# SCH_Gps_sim_locator_2022-06-02.net
KiCad netlist of a schematic drawn in EasyEDA
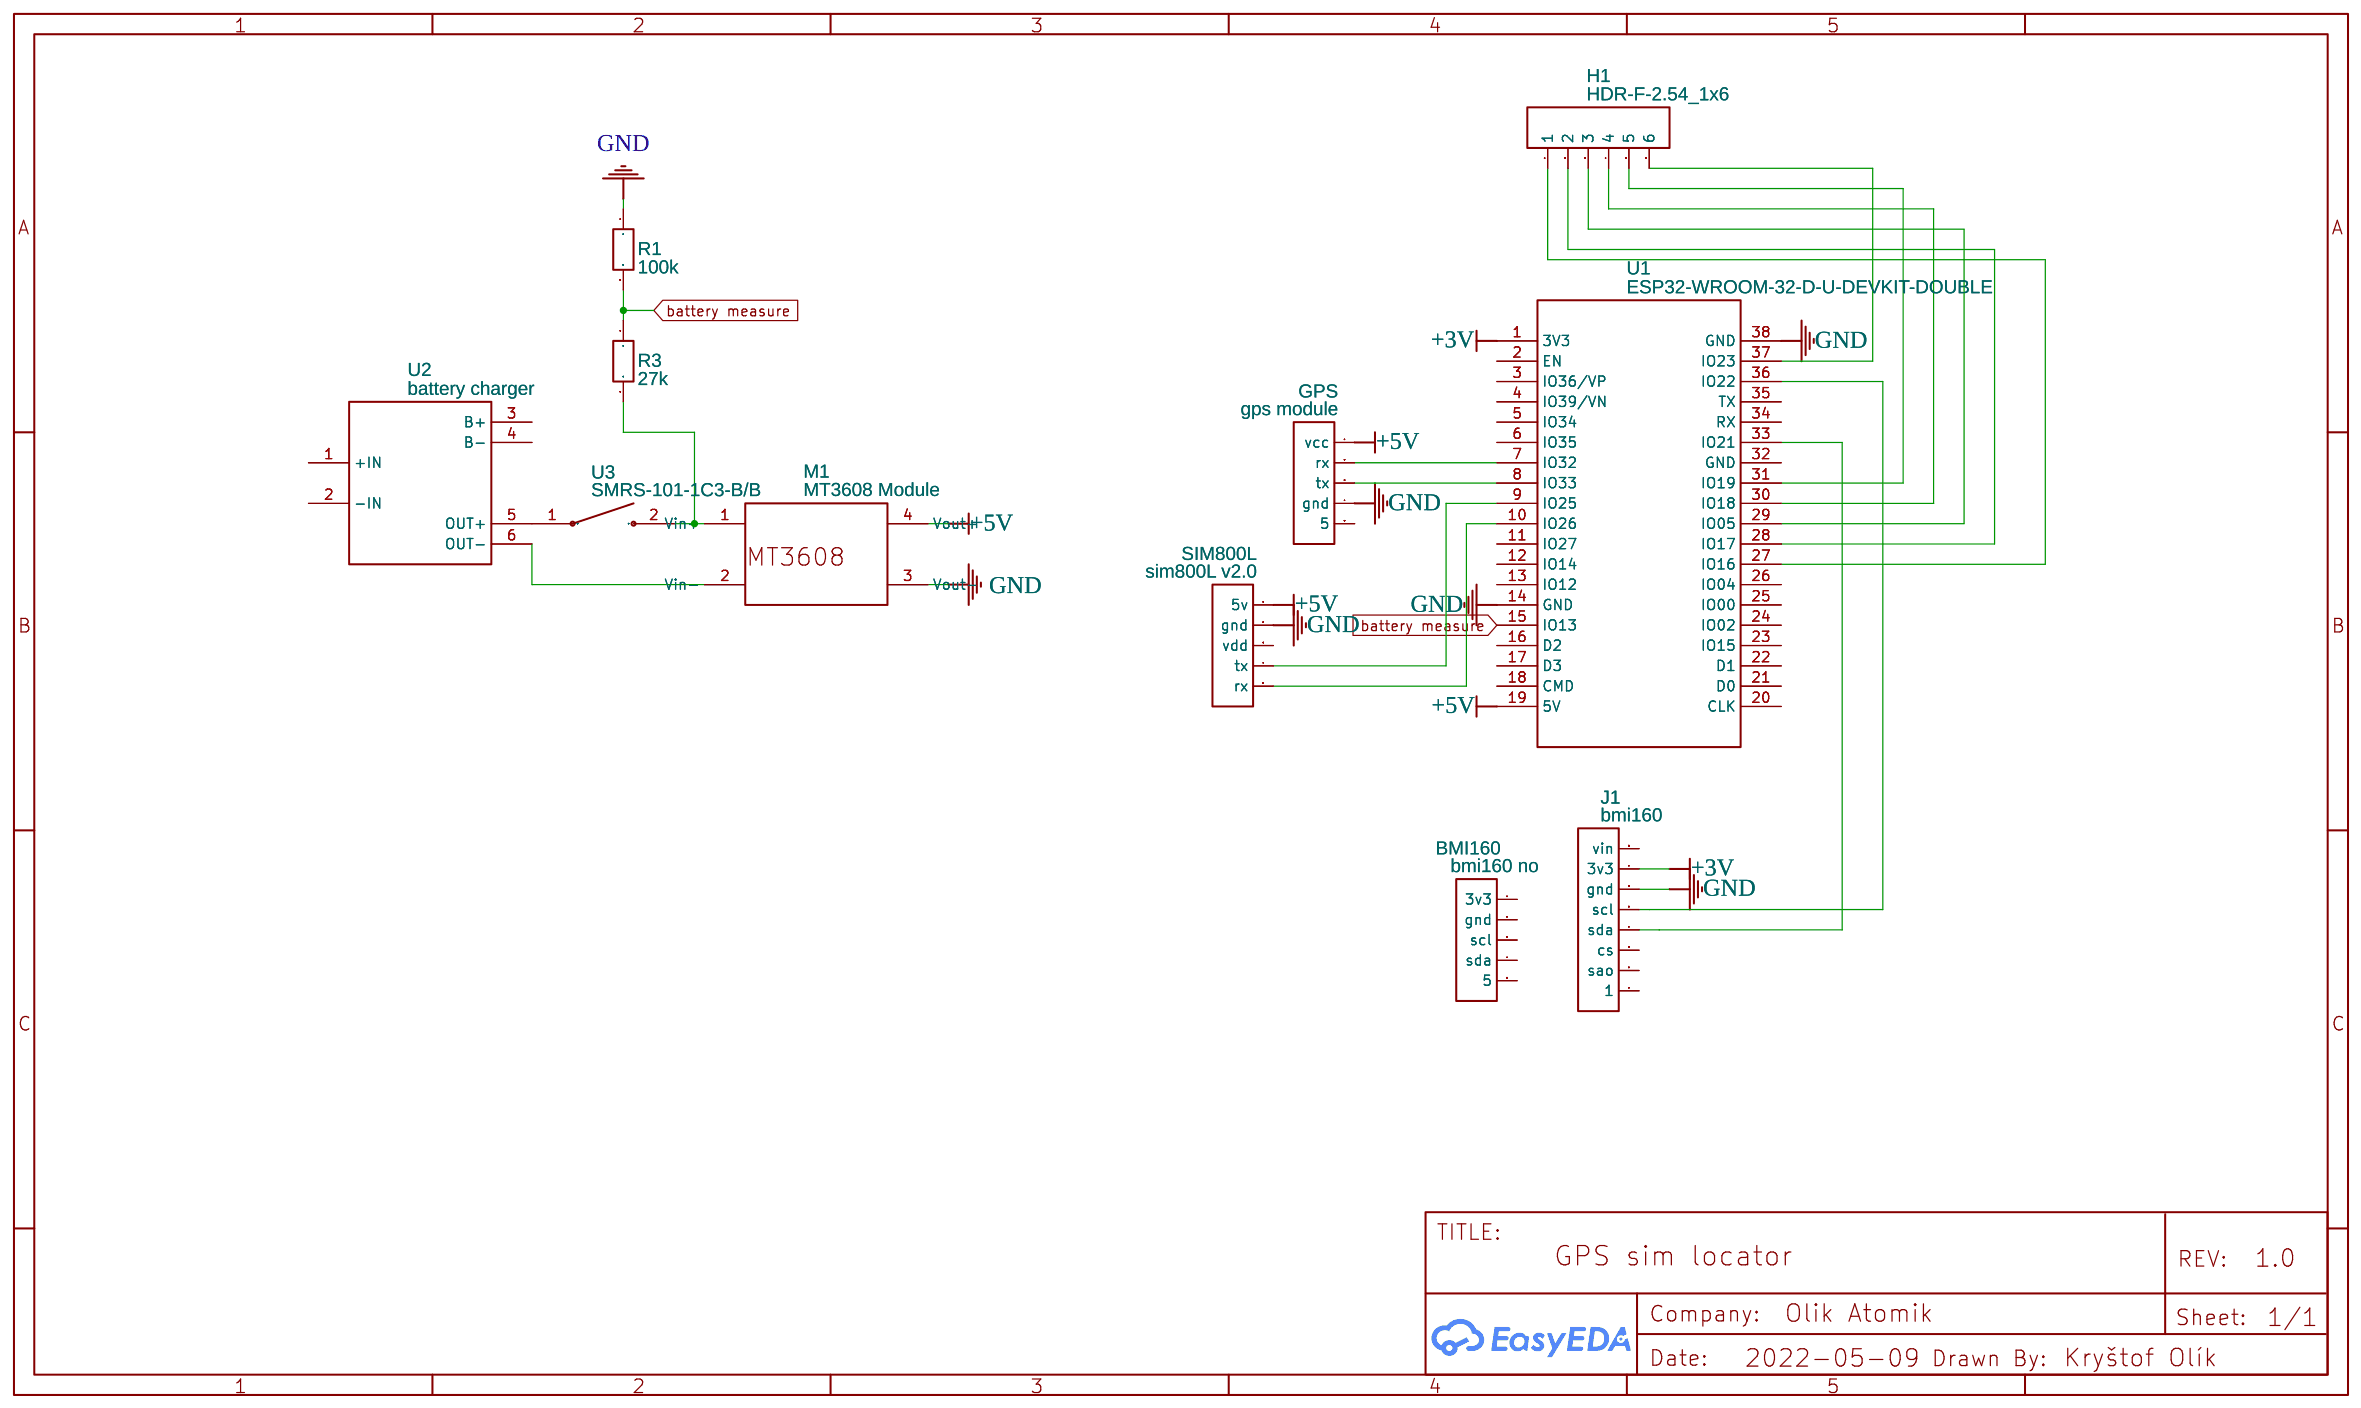
[diagram p0: schematic sheet]

(export (version "E")
  (design (tool "Eeschema 10.0.6"))
  (components
    (comp (ref "BMI160")
      (value "bmi160 no")
      (fields (field (name "BOM_Supplier Part") "C50950"))
      (libsource (lib "") (part "HDR-F-2.54_1x5_1"))
    )
    (comp (ref "GPS")
      (value "gps module")
      (fields (field (name "BOM_Supplier Part") "C50950"))
      (libsource (lib "") (part "HDR-F-2.54_1x5_2"))
    )
    (comp (ref "H1")
      (value "HDR-F-2.54_1x6")
      (fields (field (name "BOM_Supplier Part") "C40877"))
      (libsource (lib "") (part "HDR-F-2.54_1x6"))
    )
    (comp (ref "J1")
      (value "bmi160")
      (fields (field (name "BOM_Supplier Part") "C190820"))
      (libsource (lib "") (part "HDR-M-2.54_1x8"))
    )
    (comp (ref "M1") (value "MT3608 Module") (libsource (lib "") (part "MT3608 Module")))
    (comp (ref "R1") (value "100k") (libsource (lib "") (part "R_AXIAL-0.3_EU")))
    (comp (ref "R3") (value "27k") (libsource (lib "") (part "R_AXIAL-0.3_EU")))
    (comp (ref "SIM800L")
      (value "sim800L v2.0")
      (fields (field (name "BOM_Supplier Part") "C50950"))
      (libsource (lib "") (part "HDR-F-2.54_1x5"))
    )
    (comp (ref "U1")
      (value "ESP32-WROOM-32-D-U-DEVKIT-DOUBLE")
      (libsource (lib "") (part "ESP32-WROOM-32-D-U-DEVKIT-DOUBLE"))
    )
    (comp (ref "U2") (value "battery charger") (libsource (lib "") (part "TP4056 COPY")))
    (comp (ref "U3") (value "SMRS-101-1C3-B/B") (libsource (lib "") (part "SMRS-101-1C3-B/B")))
  )
  (nets
    (net (code "1") (name "+3V") (class "Default")
      (node (ref "J1") (pin "7") (pinfunction "3v3_7") (pintype "unspecified"))
      (node (ref "U1") (pin "1") (pinfunction "3V3_1") (pintype "unspecified"))
    )
    (net (code "2") (name "+5V") (class "Default")
      (node (ref "GPS") (pin "1") (pinfunction "vcc_1") (pintype "unspecified"))
      (node (ref "M1") (pin "4") (pinfunction "Vout+_4") (pintype "unspecified"))
      (node (ref "SIM800L") (pin "1") (pinfunction "5v_1") (pintype "unspecified"))
      (node (ref "U1") (pin "19") (pinfunction "5V_19") (pintype "unspecified"))
    )
    (net (code "3") (name "GND") (class "Default")
      (node (ref "GPS") (pin "4") (pinfunction "gnd_4") (pintype "unspecified"))
      (node (ref "J1") (pin "6") (pinfunction "gnd_6") (pintype "unspecified"))
      (node (ref "M1") (pin "3") (pinfunction "Vout-_3") (pintype "unspecified"))
      (node (ref "R1") (pin "1") (pinfunction "1_1") (pintype "unspecified"))
      (node (ref "SIM800L") (pin "2") (pinfunction "gnd_2") (pintype "unspecified"))
      (node (ref "U1") (pin "14") (pinfunction "GND_14") (pintype "unspecified"))
      (node (ref "U1") (pin "38") (pinfunction "GND_38") (pintype "unspecified"))
    )
    (net (code "4") (name "Net-(GPS-rx)") (class "Default")
      (node (ref "GPS") (pin "2") (pinfunction "rx_2") (pintype "unspecified"))
      (node (ref "U1") (pin "7") (pinfunction "IO32_7") (pintype "unspecified"))
    )
    (net (code "5") (name "Net-(GPS-tx)") (class "Default")
      (node (ref "GPS") (pin "3") (pinfunction "tx_3") (pintype "unspecified"))
      (node (ref "U1") (pin "8") (pinfunction "IO33_8") (pintype "unspecified"))
    )
    (net (code "6") (name "Net-(J1-scl)") (class "Default")
      (node (ref "J1") (pin "5") (pinfunction "scl_5") (pintype "unspecified"))
      (node (ref "U1") (pin "36") (pinfunction "IO22_36") (pintype "unspecified"))
    )
    (net (code "7") (name "Net-(J1-sda)") (class "Default")
      (node (ref "J1") (pin "4") (pinfunction "sda_4") (pintype "unspecified"))
      (node (ref "U1") (pin "33") (pinfunction "IO21_33") (pintype "unspecified"))
    )
    (net (code "8") (name "Net-(M1-Vin-)") (class "Default")
      (node (ref "M1") (pin "2") (pinfunction "Vin-_2") (pintype "unspecified"))
      (node (ref "U2") (pin "6") (pinfunction "OUT-_6") (pintype "unspecified"))
    )
    (net (code "9") (name "Net-(R3-Pad2)") (class "Default")
      (node (ref "R3") (pin "2") (pinfunction "2_2") (pintype "unspecified"))
      (node (ref "U3") (pin "2") (pinfunction "2_2") (pintype "unspecified"))
    )
    (net (code "10") (name "Net-(SIM800L-rx)") (class "Default")
      (node (ref "SIM800L") (pin "5") (pinfunction "rx_5") (pintype "unspecified"))
      (node (ref "U1") (pin "10") (pinfunction "IO26_10") (pintype "unspecified"))
    )
    (net (code "11") (name "Net-(SIM800L-tx)") (class "Default")
      (node (ref "SIM800L") (pin "4") (pinfunction "tx_4") (pintype "unspecified"))
      (node (ref "U1") (pin "9") (pinfunction "IO25_9") (pintype "unspecified"))
    )
    (net (code "12") (name "Net-(U1-IO05)") (class "Default")
      (node (ref "H1") (pin "3") (pinfunction "3_3") (pintype "input"))
      (node (ref "U1") (pin "29") (pinfunction "IO05_29") (pintype "unspecified"))
    )
    (net (code "13") (name "Net-(U1-IO16)") (class "Default")
      (node (ref "H1") (pin "1") (pinfunction "1_1") (pintype "input"))
      (node (ref "U1") (pin "27") (pinfunction "IO16_27") (pintype "unspecified"))
    )
    (net (code "14") (name "Net-(U1-IO17)") (class "Default")
      (node (ref "H1") (pin "2") (pinfunction "2_2") (pintype "input"))
      (node (ref "U1") (pin "28") (pinfunction "IO17_28") (pintype "unspecified"))
    )
    (net (code "15") (name "Net-(U1-IO18)") (class "Default")
      (node (ref "H1") (pin "4") (pinfunction "4_4") (pintype "input"))
      (node (ref "U1") (pin "30") (pinfunction "IO18_30") (pintype "unspecified"))
    )
    (net (code "16") (name "Net-(U1-IO19)") (class "Default")
      (node (ref "H1") (pin "5") (pinfunction "5_5") (pintype "input"))
      (node (ref "U1") (pin "31") (pinfunction "IO19_31") (pintype "unspecified"))
    )
    (net (code "17") (name "Net-(U1-IO23)") (class "Default")
      (node (ref "H1") (pin "6") (pinfunction "6_6") (pintype "input"))
      (node (ref "U1") (pin "37") (pinfunction "IO23_37") (pintype "unspecified"))
    )
    (net (code "18") (name "Net-(U2-OUT+)") (class "Default")
      (node (ref "U2") (pin "5") (pinfunction "OUT+_5") (pintype "unspecified"))
      (node (ref "U3") (pin "1") (pinfunction "in_1") (pintype "unspecified"))
    )
    (net (code "19") (name "battery measure") (class "Default")
      (node (ref "R1") (pin "2") (pinfunction "2_2") (pintype "unspecified"))
      (node (ref "R3") (pin "1") (pinfunction "1_1") (pintype "unspecified"))
      (node (ref "U1") (pin "15") (pinfunction "IO13_15") (pintype "unspecified"))
    )
    (net (code "20") (name "unconnected-(BMI160-3v3-Pad1)") (class "Default")
      (node (ref "BMI160") (pin "1") (pinfunction "3v3_1") (pintype "unspecified"))
    )
    (net (code "21") (name "unconnected-(BMI160-Pad5)") (class "Default")
      (node (ref "BMI160") (pin "5") (pinfunction "5_5") (pintype "unspecified"))
    )
    (net (code "22") (name "unconnected-(BMI160-gnd-Pad2)") (class "Default")
      (node (ref "BMI160") (pin "2") (pinfunction "gnd_2") (pintype "unspecified"))
    )
    (net (code "23") (name "unconnected-(BMI160-scl-Pad3)") (class "Default")
      (node (ref "BMI160") (pin "3") (pinfunction "scl_3") (pintype "unspecified"))
    )
    (net (code "24") (name "unconnected-(BMI160-sda-Pad4)") (class "Default")
      (node (ref "BMI160") (pin "4") (pinfunction "sda_4") (pintype "unspecified"))
    )
    (net (code "25") (name "unconnected-(GPS-Pad5)") (class "Default")
      (node (ref "GPS") (pin "5") (pinfunction "5_5") (pintype "unspecified"))
    )
    (net (code "26") (name "unconnected-(J1-Pad1)") (class "Default")
      (node (ref "J1") (pin "1") (pinfunction "1_1") (pintype "unspecified"))
    )
    (net (code "27") (name "unconnected-(J1-cs-Pad3)") (class "Default")
      (node (ref "J1") (pin "3") (pinfunction "cs_3") (pintype "unspecified"))
    )
    (net (code "28") (name "unconnected-(J1-sao-Pad2)") (class "Default")
      (node (ref "J1") (pin "2") (pinfunction "sao_2") (pintype "unspecified"))
    )
    (net (code "29") (name "unconnected-(J1-vin-Pad8)") (class "Default")
      (node (ref "J1") (pin "8") (pinfunction "vin_8") (pintype "unspecified"))
    )
    (net (code "30") (name "unconnected-(M1-Vin+-Pad1)") (class "Default")
      (node (ref "M1") (pin "1") (pinfunction "Vin+_1") (pintype "unspecified"))
    )
    (net (code "31") (name "unconnected-(SIM800L-vdd-Pad3)") (class "Default")
      (node (ref "SIM800L") (pin "3") (pinfunction "vdd_3") (pintype "unspecified"))
    )
    (net (code "32") (name "unconnected-(U1-CLK-Pad20)") (class "Default")
      (node (ref "U1") (pin "20") (pinfunction "CLK_20") (pintype "unspecified"))
    )
    (net (code "33") (name "unconnected-(U1-CMD-Pad18)") (class "Default")
      (node (ref "U1") (pin "18") (pinfunction "CMD_18") (pintype "unspecified"))
    )
    (net (code "34") (name "unconnected-(U1-D0-Pad21)") (class "Default")
      (node (ref "U1") (pin "21") (pinfunction "D0_21") (pintype "unspecified"))
    )
    (net (code "35") (name "unconnected-(U1-D1-Pad22)") (class "Default")
      (node (ref "U1") (pin "22") (pinfunction "D1_22") (pintype "unspecified"))
    )
    (net (code "36") (name "unconnected-(U1-D2-Pad16)") (class "Default")
      (node (ref "U1") (pin "16") (pinfunction "D2_16") (pintype "unspecified"))
    )
    (net (code "37") (name "unconnected-(U1-D3-Pad17)") (class "Default")
      (node (ref "U1") (pin "17") (pinfunction "D3_17") (pintype "unspecified"))
    )
    (net (code "38") (name "unconnected-(U1-EN-Pad2)") (class "Default")
      (node (ref "U1") (pin "2") (pinfunction "EN_2") (pintype "unspecified"))
    )
    (net (code "39") (name "unconnected-(U1-GND-Pad32)") (class "Default")
      (node (ref "U1") (pin "32") (pinfunction "GND_32") (pintype "unspecified"))
    )
    (net (code "40") (name "unconnected-(U1-IO00-Pad25)") (class "Default")
      (node (ref "U1") (pin "25") (pinfunction "IO00_25") (pintype "unspecified"))
    )
    (net (code "41") (name "unconnected-(U1-IO02-Pad24)") (class "Default")
      (node (ref "U1") (pin "24") (pinfunction "IO02_24") (pintype "unspecified"))
    )
    (net (code "42") (name "unconnected-(U1-IO04-Pad26)") (class "Default")
      (node (ref "U1") (pin "26") (pinfunction "IO04_26") (pintype "unspecified"))
    )
    (net (code "43") (name "unconnected-(U1-IO12-Pad13)") (class "Default")
      (node (ref "U1") (pin "13") (pinfunction "IO12_13") (pintype "unspecified"))
    )
    (net (code "44") (name "unconnected-(U1-IO14-Pad12)") (class "Default")
      (node (ref "U1") (pin "12") (pinfunction "IO14_12") (pintype "unspecified"))
    )
    (net (code "45") (name "unconnected-(U1-IO15-Pad23)") (class "Default")
      (node (ref "U1") (pin "23") (pinfunction "IO15_23") (pintype "unspecified"))
    )
    (net (code "46") (name "unconnected-(U1-IO27-Pad11)") (class "Default")
      (node (ref "U1") (pin "11") (pinfunction "IO27_11") (pintype "unspecified"))
    )
    (net (code "47") (name "unconnected-(U1-IO34-Pad5)") (class "Default")
      (node (ref "U1") (pin "5") (pinfunction "IO34_5") (pintype "unspecified"))
    )
    (net (code "48") (name "unconnected-(U1-IO35-Pad6)") (class "Default")
      (node (ref "U1") (pin "6") (pinfunction "IO35_6") (pintype "unspecified"))
    )
    (net (code "49") (name "unconnected-(U1-IO36{slash}VP-Pad3)") (class "Default")
      (node (ref "U1") (pin "3") (pinfunction "IO36/VP_3") (pintype "unspecified"))
    )
    (net (code "50") (name "unconnected-(U1-IO39{slash}VN-Pad4)") (class "Default")
      (node (ref "U1") (pin "4") (pinfunction "IO39/VN_4") (pintype "unspecified"))
    )
    (net (code "51") (name "unconnected-(U1-RX-Pad34)") (class "Default")
      (node (ref "U1") (pin "34") (pinfunction "RX_34") (pintype "unspecified"))
    )
    (net (code "52") (name "unconnected-(U1-TX-Pad35)") (class "Default")
      (node (ref "U1") (pin "35") (pinfunction "TX_35") (pintype "unspecified"))
    )
    (net (code "53") (name "unconnected-(U2-+IN-Pad1)") (class "Default")
      (node (ref "U2") (pin "1") (pinfunction "+IN_1") (pintype "unspecified"))
    )
    (net (code "54") (name "unconnected-(U2--IN-Pad2)") (class "Default")
      (node (ref "U2") (pin "2") (pinfunction "-IN_2") (pintype "unspecified"))
    )
    (net (code "55") (name "unconnected-(U2-B+-Pad3)") (class "Default")
      (node (ref "U2") (pin "3") (pinfunction "B+_3") (pintype "unspecified"))
    )
    (net (code "56") (name "unconnected-(U2-B--Pad4)") (class "Default")
      (node (ref "U2") (pin "4") (pinfunction "B-_4") (pintype "unspecified"))
    )
  )
)
